# INA219.net
KiCad netlist of a schematic drawn in EAGLE
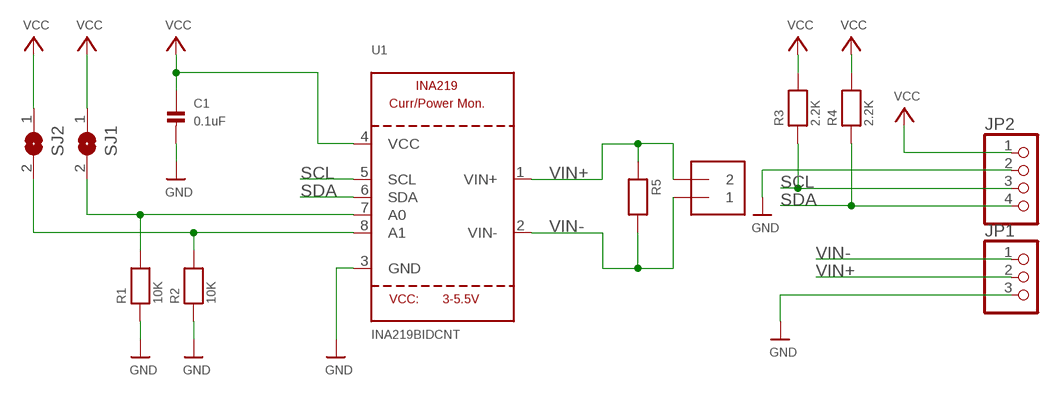
[diagram p0: schematic, sheet 1]

(export (version "E")
  (design (tool "Eeschema 10.0.6"))
  (components
    (comp (ref "C1")
      (value "0.1uF")
      (footprint "eagle-import:0805")
      (libsource (lib "eagle-import") (part "CAP_CERAMIC0805"))
    )
    (comp (ref "J1")
      (value "TERMBLOCK_1X2-3.5MM")
      (footprint "eagle-import:1X2-3.5MM")
      (libsource (lib "eagle-import") (part "TERMBLOCK_1X2-3.5MM"))
    )
    (comp (ref "JP1")
      (value "PINHD-1X3")
      (footprint "eagle-import:1X03")
      (libsource (lib "eagle-import") (part "PINHD-1X3"))
    )
    (comp (ref "JP2")
      (value "PINHD-1X4")
      (footprint "eagle-import:1X04")
      (libsource (lib "eagle-import") (part "PINHD-1X4"))
    )
    (comp (ref "R1")
      (value "10K")
      (footprint "eagle-import:0805")
      (libsource (lib "eagle-import") (part "RESISTOR0805"))
    )
    (comp (ref "R2")
      (value "10K")
      (footprint "eagle-import:0805")
      (libsource (lib "eagle-import") (part "RESISTOR0805"))
    )
    (comp (ref "R3")
      (value "2.2K")
      (footprint "eagle-import:0805")
      (libsource (lib "eagle-import") (part "RESISTOR0805"))
    )
    (comp (ref "R4")
      (value "2.2K")
      (footprint "eagle-import:0805")
      (libsource (lib "eagle-import") (part "RESISTOR0805"))
    )
    (comp (ref "R5")
      (value "RESISTOR2512")
      (footprint "eagle-import:2512")
      (libsource (lib "eagle-import") (part "RESISTOR2512"))
    )
    (comp (ref "SJ1")
      (value "SOLDERJUMPERREFLOW_NOPASTE")
      (footprint "eagle-import:SOLDERJUMPER_REFLOW_NOPASTE")
      (libsource (lib "eagle-import") (part "SOLDERJUMPERREFLOW_NOPASTE"))
    )
    (comp (ref "SJ2")
      (value "SOLDERJUMPERREFLOW_NOPASTE")
      (footprint "eagle-import:SOLDERJUMPER_REFLOW_NOPASTE")
      (libsource (lib "eagle-import") (part "SOLDERJUMPERREFLOW_NOPASTE"))
    )
    (comp (ref "U1")
      (value "INA219BIDCNT")
      (footprint "eagle-import:SOT23-8")
      (libsource (lib "eagle-import") (part "INA219"))
    )
  )
  (nets
    (net (code "1") (name "/SCL") (class "Default")
      (node (ref "JP2") (pin "3") (pinfunction "3_3") (pintype "passive"))
      (node (ref "R3") (pin "1") (pinfunction "1_1") (pintype "passive"))
      (node (ref "U1") (pin "5") (pinfunction "SCL_5") (pintype "bidirectional"))
    )
    (net (code "2") (name "/SDA") (class "Default")
      (node (ref "JP2") (pin "4") (pinfunction "4_4") (pintype "passive"))
      (node (ref "R4") (pin "1") (pinfunction "1_1") (pintype "passive"))
      (node (ref "U1") (pin "6") (pinfunction "SDA_6") (pintype "bidirectional"))
    )
    (net (code "3") (name "/VIN+") (class "Default")
      (node (ref "J1") (pin "2") (pinfunction "2_2") (pintype "passive"))
      (node (ref "JP1") (pin "2") (pinfunction "2_2") (pintype "passive"))
      (node (ref "R5") (pin "1") (pinfunction "1_1") (pintype "passive"))
      (node (ref "U1") (pin "1") (pinfunction "VIN+_1") (pintype "bidirectional"))
    )
    (net (code "4") (name "/VIN-") (class "Default")
      (node (ref "J1") (pin "1") (pinfunction "1_1") (pintype "passive"))
      (node (ref "JP1") (pin "1") (pinfunction "1_1") (pintype "passive"))
      (node (ref "R5") (pin "2") (pinfunction "2_2") (pintype "passive"))
      (node (ref "U1") (pin "2") (pinfunction "VIN-_2") (pintype "bidirectional"))
    )
    (net (code "5") (name "GND") (class "Default")
      (node (ref "C1") (pin "2") (pinfunction "P$2_2") (pintype "passive"))
      (node (ref "JP1") (pin "3") (pinfunction "3_3") (pintype "passive"))
      (node (ref "JP2") (pin "2") (pinfunction "2_2") (pintype "passive"))
      (node (ref "R1") (pin "1") (pinfunction "1_1") (pintype "passive"))
      (node (ref "R2") (pin "1") (pinfunction "1_1") (pintype "passive"))
      (node (ref "U1") (pin "3") (pinfunction "GND_3") (pintype "bidirectional"))
    )
    (net (code "6") (name "Net-(U1-A0)") (class "Default")
      (node (ref "R1") (pin "2") (pinfunction "2_2") (pintype "passive"))
      (node (ref "SJ1") (pin "2") (pinfunction "2_2") (pintype "passive"))
      (node (ref "U1") (pin "7") (pinfunction "A0_7") (pintype "bidirectional"))
    )
    (net (code "7") (name "Net-(U1-A1)") (class "Default")
      (node (ref "R2") (pin "2") (pinfunction "2_2") (pintype "passive"))
      (node (ref "SJ2") (pin "2") (pinfunction "2_2") (pintype "passive"))
      (node (ref "U1") (pin "8") (pinfunction "A1_8") (pintype "bidirectional"))
    )
    (net (code "8") (name "VCC") (class "Default")
      (node (ref "C1") (pin "1") (pinfunction "P$1_1") (pintype "passive"))
      (node (ref "JP2") (pin "1") (pinfunction "1_1") (pintype "passive"))
      (node (ref "R3") (pin "2") (pinfunction "2_2") (pintype "passive"))
      (node (ref "R4") (pin "2") (pinfunction "2_2") (pintype "passive"))
      (node (ref "SJ1") (pin "1") (pinfunction "1_1") (pintype "passive"))
      (node (ref "SJ2") (pin "1") (pinfunction "1_1") (pintype "passive"))
      (node (ref "U1") (pin "4") (pinfunction "VCC_4") (pintype "bidirectional"))
    )
  )
)
